# IV_Swinger_2_fet_mod.net
KiCad netlist of a schematic drawn in EAGLE
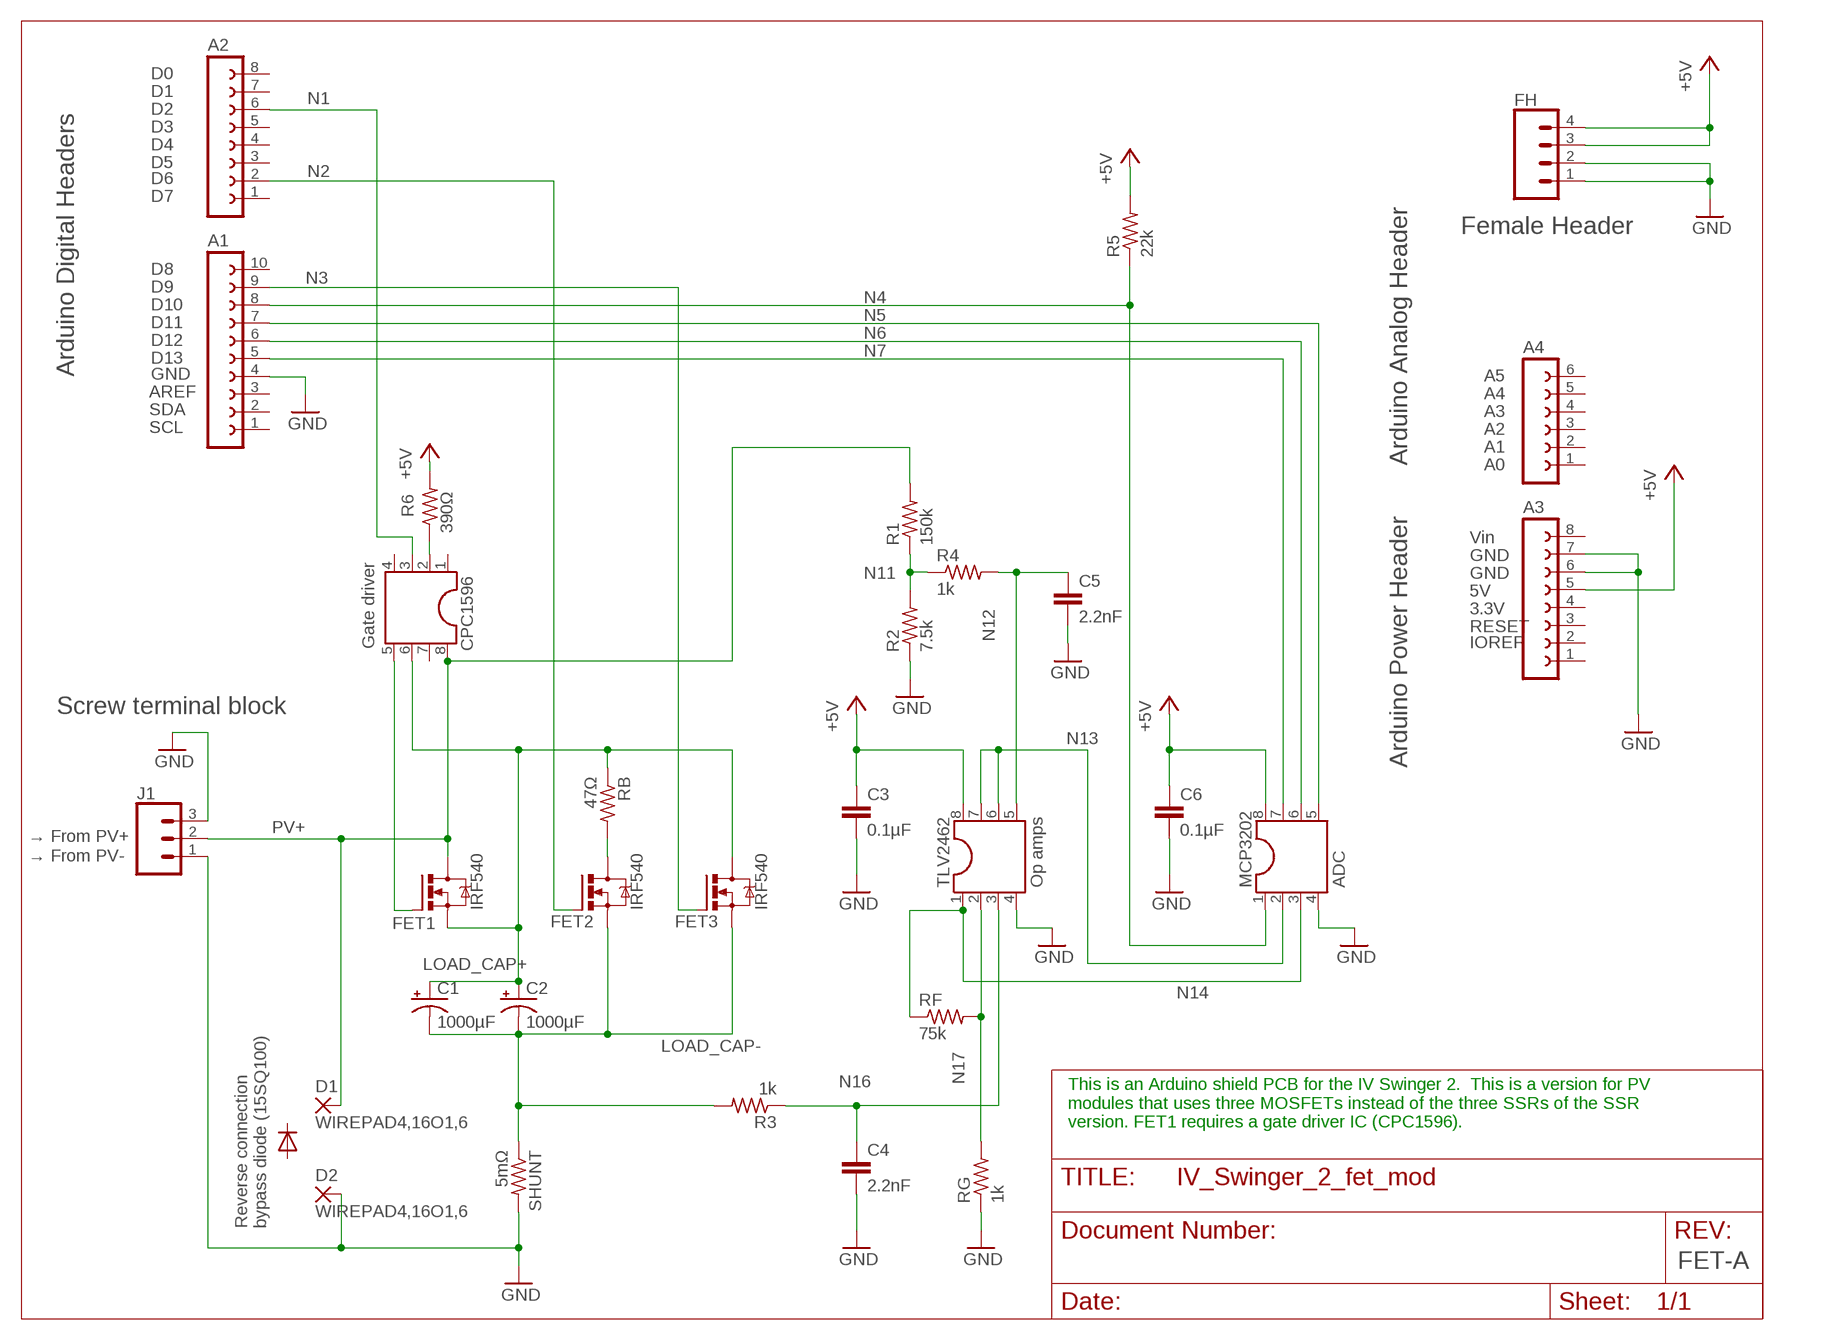
[diagram p0: schematic, sheet 1]

(export (version "E")
  (design (tool "Eeschema 10.0.6"))
  (components
    (comp (ref "A1")
      (value "FE10-1")
      (footprint "eagle-import:FE10")
      (libsource (lib "eagle-import") (part "FE10-1"))
    )
    (comp (ref "A2")
      (value "FE08-1")
      (footprint "eagle-import:FE08")
      (libsource (lib "eagle-import") (part "FE08-1"))
    )
    (comp (ref "A3")
      (value "FE08-1")
      (footprint "eagle-import:FE08")
      (libsource (lib "eagle-import") (part "FE08-1"))
    )
    (comp (ref "A4")
      (value "FE06-1")
      (footprint "eagle-import:FE06")
      (libsource (lib "eagle-import") (part "FE06-1"))
    )
    (comp (ref "C1")
      (value "1000µF")
      (footprint "eagle-import:E7,5-18")
      (libsource (lib "eagle-import") (part "CPOL-USE7.5-18"))
    )
    (comp (ref "C2")
      (value "1000µF")
      (footprint "eagle-import:E7,5-18")
      (libsource (lib "eagle-import") (part "CPOL-USE7.5-18"))
    )
    (comp (ref "C3")
      (value "0.1µF")
      (footprint "eagle-import:C025-030X050")
      (libsource (lib "eagle-import") (part "C-EU025-030X050"))
    )
    (comp (ref "C4")
      (value "2.2nF")
      (footprint "eagle-import:C025-030X050")
      (libsource (lib "eagle-import") (part "C-EU025-030X050"))
    )
    (comp (ref "C5")
      (value "2.2nF")
      (footprint "eagle-import:C025-030X050")
      (libsource (lib "eagle-import") (part "C-EU025-030X050"))
    )
    (comp (ref "C6")
      (value "0.1µF")
      (footprint "eagle-import:C025-030X050")
      (libsource (lib "eagle-import") (part "C-EU025-030X050"))
    )
    (comp (ref "CPC1596")
      (value "Gate driver")
      (footprint "eagle-import:SOCKET-08")
      (libsource (lib "eagle-import") (part "DIL8S"))
    )
    (comp (ref "D1")
      (value "WIREPAD4,16O1,6")
      (footprint "eagle-import:4,16O1,6")
      (fields (field (name "SPICEPREFIX") "X"))
      (libsource (lib "eagle-import") (part "WIREPAD4,16O1,6"))
    )
    (comp (ref "D2")
      (value "WIREPAD4,16O1,6")
      (footprint "eagle-import:4,16O1,6")
      (libsource (lib "eagle-import") (part "WIREPAD4,16O1,6"))
    )
    (comp (ref "FET1")
      (value "IRF540")
      (footprint "eagle-import:TO220BV")
      (libsource (lib "eagle-import") (part "IRF540"))
    )
    (comp (ref "FET2")
      (value "IRF540")
      (footprint "eagle-import:TO220BV")
      (libsource (lib "eagle-import") (part "IRF540"))
    )
    (comp (ref "FET3")
      (value "IRF540")
      (footprint "eagle-import:TO220BV")
      (libsource (lib "eagle-import") (part "IRF540"))
    )
    (comp (ref "FH")
      (value "CONN_04LONGPADS")
      (footprint "eagle-import:1X04_LONGPADS")
      (libsource (lib "eagle-import") (part "CONN_04LONGPADS"))
    )
    (comp (ref "J1")
      (value "CONN_03-SCREW-5MM")
      (footprint "eagle-import:SCREWTERMINAL-5MM-3")
      (libsource (lib "eagle-import") (part "CONN_03-SCREW-5MM"))
    )
    (comp (ref "MCP3202")
      (value "ADC")
      (footprint "eagle-import:SOCKET-08")
      (libsource (lib "eagle-import") (part "DIL8S"))
    )
    (comp (ref "R1")
      (value "150k")
      (footprint "eagle-import:0207_10")
      (libsource (lib "eagle-import") (part "R-US_0207/10"))
    )
    (comp (ref "R2")
      (value "7.5k")
      (footprint "eagle-import:0207_10")
      (libsource (lib "eagle-import") (part "R-US_0207/10"))
    )
    (comp (ref "R3")
      (value "1k")
      (footprint "eagle-import:0207_10")
      (libsource (lib "eagle-import") (part "R-US_0207/10"))
    )
    (comp (ref "R4")
      (value "1k")
      (footprint "eagle-import:0207_10")
      (libsource (lib "eagle-import") (part "R-US_0207/10"))
    )
    (comp (ref "R5")
      (value "22k")
      (footprint "eagle-import:0207_10")
      (libsource (lib "eagle-import") (part "R-US_0207/10"))
    )
    (comp (ref "R6")
      (value "390Ω")
      (footprint "eagle-import:0207_10")
      (libsource (lib "eagle-import") (part "R-US_0207/10"))
    )
    (comp (ref "RB")
      (value "47Ω")
      (footprint "eagle-import:P0817V")
      (libsource (lib "eagle-import") (part "R-US_0817/7V"))
    )
    (comp (ref "RF")
      (value "75k")
      (footprint "eagle-import:0207_10")
      (libsource (lib "eagle-import") (part "R-US_0207/10"))
    )
    (comp (ref "RG")
      (value "1k")
      (footprint "eagle-import:0207_10")
      (libsource (lib "eagle-import") (part "R-US_0207/10"))
    )
    (comp (ref "SHUNT")
      (value "5mΩ")
      (footprint "eagle-import:0617V")
      (libsource (lib "eagle-import") (part "R-US_0617/5V"))
    )
    (comp (ref "TLV2462")
      (value "Op amps")
      (footprint "eagle-import:SOCKET-08")
      (libsource (lib "eagle-import") (part "DIL8S"))
    )
  )
  (nets
    (net (code "1") (name "+5V") (class "Default")
      (node (ref "A3") (pin "5") (pinfunction "5_5") (pintype "passive"))
      (node (ref "C3") (pin "1") (pinfunction "1_1") (pintype "passive"))
      (node (ref "C6") (pin "1") (pinfunction "1_1") (pintype "passive"))
      (node (ref "FH") (pin "3") (pinfunction "3_3") (pintype "passive"))
      (node (ref "FH") (pin "4") (pinfunction "4_4") (pintype "passive"))
      (node (ref "MCP3202") (pin "8") (pinfunction "8_8") (pintype "passive"))
      (node (ref "R5") (pin "2") (pinfunction "2_2") (pintype "passive"))
      (node (ref "R6") (pin "2") (pinfunction "2_2") (pintype "passive"))
      (node (ref "TLV2462") (pin "8") (pinfunction "8_8") (pintype "passive"))
    )
    (net (code "2") (name "/LOAD_CAP+") (class "Default")
      (node (ref "C1") (pin "+") (pinfunction "+_+") (pintype "passive"))
      (node (ref "C2") (pin "+") (pinfunction "+_+") (pintype "passive"))
      (node (ref "CPC1596") (pin "6") (pinfunction "6_6") (pintype "passive"))
      (node (ref "FET1") (pin "S") (pinfunction "S_S") (pintype "passive"))
      (node (ref "FET3") (pin "D") (pinfunction "D_D") (pintype "passive"))
      (node (ref "RB") (pin "1") (pinfunction "1_1") (pintype "passive"))
    )
    (net (code "3") (name "/LOAD_CAP-") (class "Default")
      (node (ref "C1") (pin "-") (pinfunction "-_-") (pintype "passive"))
      (node (ref "C2") (pin "-") (pinfunction "-_-") (pintype "passive"))
      (node (ref "FET2") (pin "S") (pinfunction "S_S") (pintype "passive"))
      (node (ref "FET3") (pin "S") (pinfunction "S_S") (pintype "passive"))
      (node (ref "R3") (pin "2") (pinfunction "2_2") (pintype "passive"))
      (node (ref "SHUNT") (pin "1") (pinfunction "1_1") (pintype "passive"))
    )
    (net (code "4") (name "/N1") (class "Default")
      (node (ref "A2") (pin "6") (pinfunction "6_6") (pintype "passive"))
      (node (ref "CPC1596") (pin "3") (pinfunction "3_3") (pintype "passive"))
    )
    (net (code "5") (name "/N2") (class "Default")
      (node (ref "A2") (pin "2") (pinfunction "2_2") (pintype "passive"))
      (node (ref "FET2") (pin "G") (pinfunction "G_G") (pintype "passive"))
    )
    (net (code "6") (name "/N3") (class "Default")
      (node (ref "A1") (pin "9") (pinfunction "9_9") (pintype "passive"))
      (node (ref "FET3") (pin "G") (pinfunction "G_G") (pintype "passive"))
    )
    (net (code "7") (name "/N4") (class "Default")
      (node (ref "A1") (pin "8") (pinfunction "8_8") (pintype "passive"))
      (node (ref "MCP3202") (pin "1") (pinfunction "1_1") (pintype "passive"))
      (node (ref "R5") (pin "1") (pinfunction "1_1") (pintype "passive"))
    )
    (net (code "8") (name "/N5") (class "Default")
      (node (ref "A1") (pin "7") (pinfunction "7_7") (pintype "passive"))
      (node (ref "MCP3202") (pin "5") (pinfunction "5_5") (pintype "passive"))
    )
    (net (code "9") (name "/N6") (class "Default")
      (node (ref "A1") (pin "6") (pinfunction "6_6") (pintype "passive"))
      (node (ref "MCP3202") (pin "6") (pinfunction "6_6") (pintype "passive"))
    )
    (net (code "10") (name "/N7") (class "Default")
      (node (ref "A1") (pin "5") (pinfunction "5_5") (pintype "passive"))
      (node (ref "MCP3202") (pin "7") (pinfunction "7_7") (pintype "passive"))
    )
    (net (code "11") (name "/N11") (class "Default")
      (node (ref "R1") (pin "1") (pinfunction "1_1") (pintype "passive"))
      (node (ref "R2") (pin "2") (pinfunction "2_2") (pintype "passive"))
      (node (ref "R4") (pin "1") (pinfunction "1_1") (pintype "passive"))
    )
    (net (code "12") (name "/N12") (class "Default")
      (node (ref "C5") (pin "1") (pinfunction "1_1") (pintype "passive"))
      (node (ref "R4") (pin "2") (pinfunction "2_2") (pintype "passive"))
      (node (ref "TLV2462") (pin "5") (pinfunction "5_5") (pintype "passive"))
    )
    (net (code "13") (name "/N13") (class "Default")
      (node (ref "MCP3202") (pin "2") (pinfunction "2_2") (pintype "passive"))
      (node (ref "TLV2462") (pin "6") (pinfunction "6_6") (pintype "passive"))
      (node (ref "TLV2462") (pin "7") (pinfunction "7_7") (pintype "passive"))
    )
    (net (code "14") (name "/N14") (class "Default")
      (node (ref "MCP3202") (pin "3") (pinfunction "3_3") (pintype "passive"))
      (node (ref "RF") (pin "1") (pinfunction "1_1") (pintype "passive"))
      (node (ref "TLV2462") (pin "1") (pinfunction "1_1") (pintype "passive"))
    )
    (net (code "15") (name "/N16") (class "Default")
      (node (ref "C4") (pin "1") (pinfunction "1_1") (pintype "passive"))
      (node (ref "R3") (pin "1") (pinfunction "1_1") (pintype "passive"))
      (node (ref "TLV2462") (pin "3") (pinfunction "3_3") (pintype "passive"))
    )
    (net (code "16") (name "/N17") (class "Default")
      (node (ref "RF") (pin "2") (pinfunction "2_2") (pintype "passive"))
      (node (ref "RG") (pin "2") (pinfunction "2_2") (pintype "passive"))
      (node (ref "TLV2462") (pin "2") (pinfunction "2_2") (pintype "passive"))
    )
    (net (code "17") (name "/PV+") (class "Default")
      (node (ref "CPC1596") (pin "8") (pinfunction "8_8") (pintype "passive"))
      (node (ref "D1") (pin "1") (pinfunction "P_1") (pintype "passive"))
      (node (ref "FET1") (pin "D") (pinfunction "D_D") (pintype "passive"))
      (node (ref "J1") (pin "2") (pinfunction "2_2") (pintype "passive"))
      (node (ref "R1") (pin "2") (pinfunction "2_2") (pintype "passive"))
    )
    (net (code "18") (name "GND") (class "Default")
      (node (ref "A1") (pin "4") (pinfunction "4_4") (pintype "passive"))
      (node (ref "A3") (pin "6") (pinfunction "6_6") (pintype "passive"))
      (node (ref "A3") (pin "7") (pinfunction "7_7") (pintype "passive"))
      (node (ref "C3") (pin "2") (pinfunction "2_2") (pintype "passive"))
      (node (ref "C4") (pin "2") (pinfunction "2_2") (pintype "passive"))
      (node (ref "C5") (pin "2") (pinfunction "2_2") (pintype "passive"))
      (node (ref "C6") (pin "2") (pinfunction "2_2") (pintype "passive"))
      (node (ref "D2") (pin "1") (pinfunction "P_1") (pintype "passive"))
      (node (ref "FH") (pin "1") (pinfunction "1_1") (pintype "passive"))
      (node (ref "FH") (pin "2") (pinfunction "2_2") (pintype "passive"))
      (node (ref "J1") (pin "1") (pinfunction "1_1") (pintype "passive"))
      (node (ref "J1") (pin "3") (pinfunction "3_3") (pintype "passive"))
      (node (ref "MCP3202") (pin "4") (pinfunction "4_4") (pintype "passive"))
      (node (ref "R2") (pin "1") (pinfunction "1_1") (pintype "passive"))
      (node (ref "RG") (pin "1") (pinfunction "1_1") (pintype "passive"))
      (node (ref "SHUNT") (pin "2") (pinfunction "2_2") (pintype "passive"))
      (node (ref "TLV2462") (pin "4") (pinfunction "4_4") (pintype "passive"))
    )
    (net (code "19") (name "Net-(CPC1596-Pad2)") (class "Default")
      (node (ref "CPC1596") (pin "2") (pinfunction "2_2") (pintype "passive"))
      (node (ref "R6") (pin "1") (pinfunction "1_1") (pintype "passive"))
    )
    (net (code "20") (name "Net-(CPC1596-Pad5)") (class "Default")
      (node (ref "CPC1596") (pin "5") (pinfunction "5_5") (pintype "passive"))
      (node (ref "FET1") (pin "G") (pinfunction "G_G") (pintype "passive"))
    )
    (net (code "21") (name "Net-(FET2-PadD)") (class "Default")
      (node (ref "FET2") (pin "D") (pinfunction "D_D") (pintype "passive"))
      (node (ref "RB") (pin "2") (pinfunction "2_2") (pintype "passive"))
    )
    (net (code "22") (name "unconnected-(A1-Pad1)") (class "Default")
      (node (ref "A1") (pin "1") (pinfunction "1_1") (pintype "passive"))
    )
    (net (code "23") (name "unconnected-(A1-Pad2)") (class "Default")
      (node (ref "A1") (pin "2") (pinfunction "2_2") (pintype "passive"))
    )
    (net (code "24") (name "unconnected-(A1-Pad3)") (class "Default")
      (node (ref "A1") (pin "3") (pinfunction "3_3") (pintype "passive"))
    )
    (net (code "25") (name "unconnected-(A1-Pad10)") (class "Default")
      (node (ref "A1") (pin "10") (pinfunction "10_10") (pintype "passive"))
    )
    (net (code "26") (name "unconnected-(A2-Pad1)") (class "Default")
      (node (ref "A2") (pin "1") (pinfunction "1_1") (pintype "passive"))
    )
    (net (code "27") (name "unconnected-(A2-Pad3)") (class "Default")
      (node (ref "A2") (pin "3") (pinfunction "3_3") (pintype "passive"))
    )
    (net (code "28") (name "unconnected-(A2-Pad4)") (class "Default")
      (node (ref "A2") (pin "4") (pinfunction "4_4") (pintype "passive"))
    )
    (net (code "29") (name "unconnected-(A2-Pad5)") (class "Default")
      (node (ref "A2") (pin "5") (pinfunction "5_5") (pintype "passive"))
    )
    (net (code "30") (name "unconnected-(A2-Pad7)") (class "Default")
      (node (ref "A2") (pin "7") (pinfunction "7_7") (pintype "passive"))
    )
    (net (code "31") (name "unconnected-(A2-Pad8)") (class "Default")
      (node (ref "A2") (pin "8") (pinfunction "8_8") (pintype "passive"))
    )
    (net (code "32") (name "unconnected-(A3-Pad1)") (class "Default")
      (node (ref "A3") (pin "1") (pinfunction "1_1") (pintype "passive"))
    )
    (net (code "33") (name "unconnected-(A3-Pad2)") (class "Default")
      (node (ref "A3") (pin "2") (pinfunction "2_2") (pintype "passive"))
    )
    (net (code "34") (name "unconnected-(A3-Pad3)") (class "Default")
      (node (ref "A3") (pin "3") (pinfunction "3_3") (pintype "passive"))
    )
    (net (code "35") (name "unconnected-(A3-Pad4)") (class "Default")
      (node (ref "A3") (pin "4") (pinfunction "4_4") (pintype "passive"))
    )
    (net (code "36") (name "unconnected-(A3-Pad8)") (class "Default")
      (node (ref "A3") (pin "8") (pinfunction "8_8") (pintype "passive"))
    )
    (net (code "37") (name "unconnected-(A4-Pad1)") (class "Default")
      (node (ref "A4") (pin "1") (pinfunction "1_1") (pintype "passive"))
    )
    (net (code "38") (name "unconnected-(A4-Pad2)") (class "Default")
      (node (ref "A4") (pin "2") (pinfunction "2_2") (pintype "passive"))
    )
    (net (code "39") (name "unconnected-(A4-Pad3)") (class "Default")
      (node (ref "A4") (pin "3") (pinfunction "3_3") (pintype "passive"))
    )
    (net (code "40") (name "unconnected-(A4-Pad4)") (class "Default")
      (node (ref "A4") (pin "4") (pinfunction "4_4") (pintype "passive"))
    )
    (net (code "41") (name "unconnected-(A4-Pad5)") (class "Default")
      (node (ref "A4") (pin "5") (pinfunction "5_5") (pintype "passive"))
    )
    (net (code "42") (name "unconnected-(A4-Pad6)") (class "Default")
      (node (ref "A4") (pin "6") (pinfunction "6_6") (pintype "passive"))
    )
    (net (code "43") (name "unconnected-(CPC1596-Pad1)") (class "Default")
      (node (ref "CPC1596") (pin "1") (pinfunction "1_1") (pintype "passive"))
    )
    (net (code "44") (name "unconnected-(CPC1596-Pad4)") (class "Default")
      (node (ref "CPC1596") (pin "4") (pinfunction "4_4") (pintype "passive"))
    )
    (net (code "45") (name "unconnected-(CPC1596-Pad7)") (class "Default")
      (node (ref "CPC1596") (pin "7") (pinfunction "7_7") (pintype "passive"))
    )
  )
)
